# Sheet2.net
KiCad netlist of a schematic drawn in Altium Designer
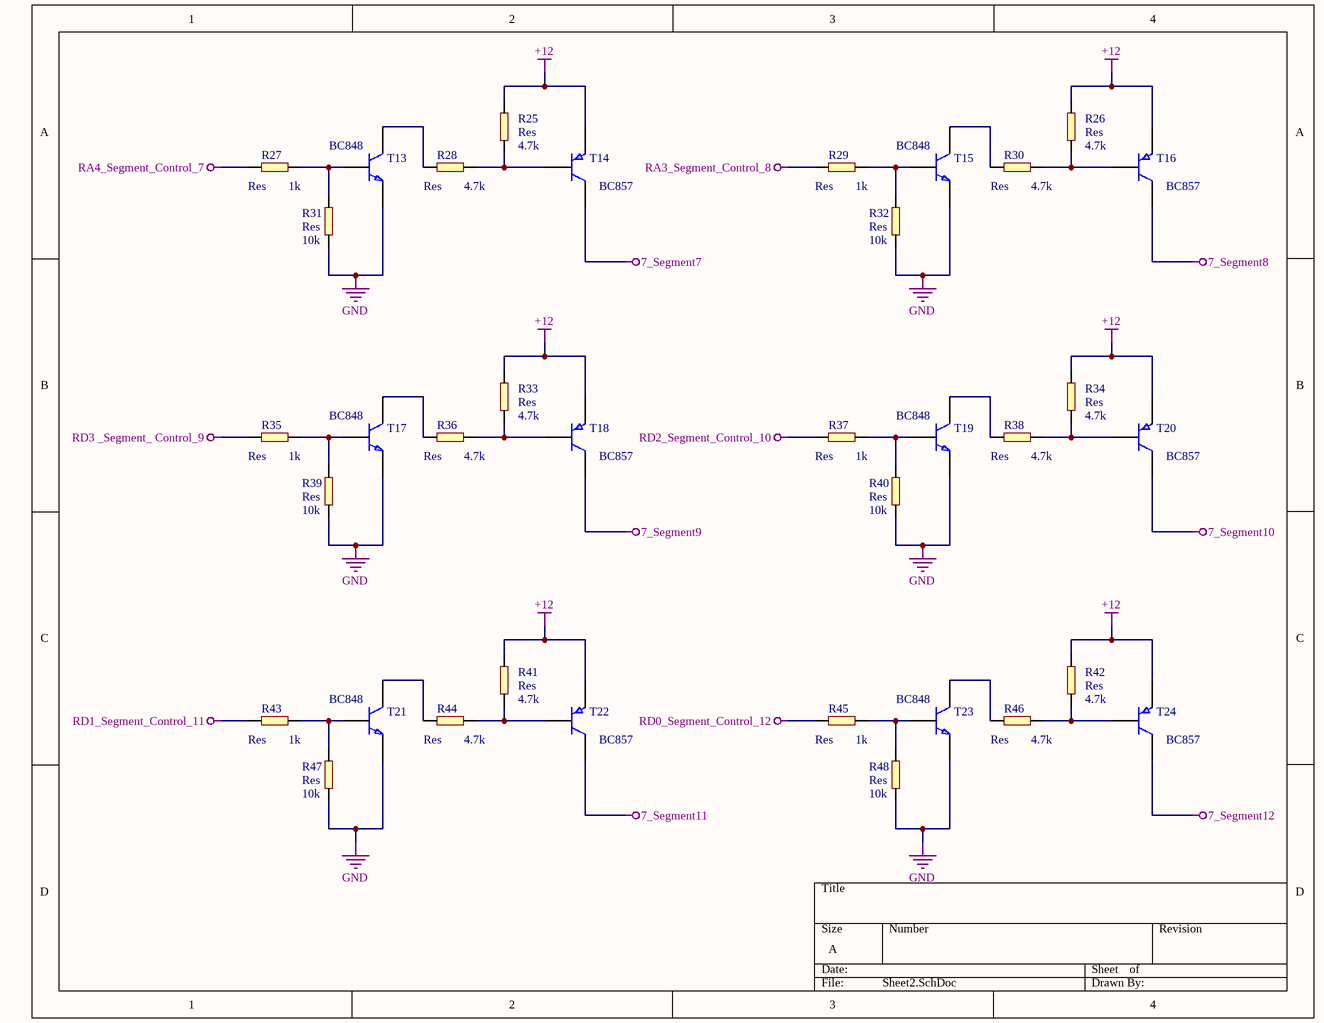
[diagram p0: Sheet2.SchDoc]

(export (version "E")
  (design (tool "Eeschema 10.0.6"))
  (components
    (comp (ref "R25")
      (value "Res")
      (footprint "RES0805")
      (description "Res0805")
      (fields (field (name "ALTIUM_VALUE") "4.7k"))
      (libsource (lib "") (part "Resistor_1"))
    )
    (comp (ref "R26")
      (value "Res")
      (footprint "RES0805")
      (description "Res0805")
      (fields (field (name "ALTIUM_VALUE") "4.7k"))
      (libsource (lib "") (part "Resistor_1"))
    )
    (comp (ref "R27")
      (value "Res")
      (footprint "RES0805")
      (description "Res0805")
      (fields (field (name "ALTIUM_VALUE") "1k"))
      (libsource (lib "Dinesh_New_Integrated_Library") (part "Resistor"))
    )
    (comp (ref "R28")
      (value "Res")
      (footprint "RES0805")
      (description "Res0805")
      (fields (field (name "ALTIUM_VALUE") "4.7k"))
      (libsource (lib "Dinesh_New_Integrated_Library") (part "Resistor"))
    )
    (comp (ref "R29")
      (value "Res")
      (footprint "RES0805")
      (description "Res0805")
      (fields (field (name "ALTIUM_VALUE") "1k"))
      (libsource (lib "Dinesh_New_Integrated_Library") (part "Resistor"))
    )
    (comp (ref "R30")
      (value "Res")
      (footprint "RES0805")
      (description "Res0805")
      (fields (field (name "ALTIUM_VALUE") "4.7k"))
      (libsource (lib "Dinesh_New_Integrated_Library") (part "Resistor"))
    )
    (comp (ref "R31")
      (value "Res")
      (footprint "RES0805")
      (description "Res0805")
      (fields (field (name "ALTIUM_VALUE") "10k"))
      (libsource (lib "") (part "Resistor_2"))
    )
    (comp (ref "R32")
      (value "Res")
      (footprint "RES0805")
      (description "Res0805")
      (fields (field (name "ALTIUM_VALUE") "10k"))
      (libsource (lib "") (part "Resistor_2"))
    )
    (comp (ref "R33")
      (value "Res")
      (footprint "RES0805")
      (description "Res0805")
      (fields (field (name "ALTIUM_VALUE") "4.7k"))
      (libsource (lib "") (part "Resistor_1"))
    )
    (comp (ref "R34")
      (value "Res")
      (footprint "RES0805")
      (description "Res0805")
      (fields (field (name "ALTIUM_VALUE") "4.7k"))
      (libsource (lib "") (part "Resistor_1"))
    )
    (comp (ref "R35")
      (value "Res")
      (footprint "RES0805")
      (description "Res0805")
      (fields (field (name "ALTIUM_VALUE") "1k"))
      (libsource (lib "Dinesh_New_Integrated_Library") (part "Resistor"))
    )
    (comp (ref "R36")
      (value "Res")
      (footprint "RES0805")
      (description "Res0805")
      (fields (field (name "ALTIUM_VALUE") "4.7k"))
      (libsource (lib "Dinesh_New_Integrated_Library") (part "Resistor"))
    )
    (comp (ref "R37")
      (value "Res")
      (footprint "RES0805")
      (description "Res0805")
      (fields (field (name "ALTIUM_VALUE") "1k"))
      (libsource (lib "Dinesh_New_Integrated_Library") (part "Resistor"))
    )
    (comp (ref "R38")
      (value "Res")
      (footprint "RES0805")
      (description "Res0805")
      (fields (field (name "ALTIUM_VALUE") "4.7k"))
      (libsource (lib "Dinesh_New_Integrated_Library") (part "Resistor"))
    )
    (comp (ref "R39")
      (value "Res")
      (footprint "RES0805")
      (description "Res0805")
      (fields (field (name "ALTIUM_VALUE") "10k"))
      (libsource (lib "") (part "Resistor_2"))
    )
    (comp (ref "R40")
      (value "Res")
      (footprint "RES0805")
      (description "Res0805")
      (fields (field (name "ALTIUM_VALUE") "10k"))
      (libsource (lib "") (part "Resistor_2"))
    )
    (comp (ref "R41")
      (value "Res")
      (footprint "RES0805")
      (description "Res0805")
      (fields (field (name "ALTIUM_VALUE") "4.7k"))
      (libsource (lib "") (part "Resistor_1"))
    )
    (comp (ref "R42")
      (value "Res")
      (footprint "RES0805")
      (description "Res0805")
      (fields (field (name "ALTIUM_VALUE") "4.7k"))
      (libsource (lib "") (part "Resistor_1"))
    )
    (comp (ref "R43")
      (value "Res")
      (footprint "RES0805")
      (description "Res0805")
      (fields (field (name "ALTIUM_VALUE") "1k"))
      (libsource (lib "Dinesh_New_Integrated_Library") (part "Resistor"))
    )
    (comp (ref "R44")
      (value "Res")
      (footprint "RES0805")
      (description "Res0805")
      (fields (field (name "ALTIUM_VALUE") "4.7k"))
      (libsource (lib "Dinesh_New_Integrated_Library") (part "Resistor"))
    )
    (comp (ref "R45")
      (value "Res")
      (footprint "RES0805")
      (description "Res0805")
      (fields (field (name "ALTIUM_VALUE") "1k"))
      (libsource (lib "Dinesh_New_Integrated_Library") (part "Resistor"))
    )
    (comp (ref "R46")
      (value "Res")
      (footprint "RES0805")
      (description "Res0805")
      (fields (field (name "ALTIUM_VALUE") "4.7k"))
      (libsource (lib "Dinesh_New_Integrated_Library") (part "Resistor"))
    )
    (comp (ref "R47")
      (value "Res")
      (footprint "RES0805")
      (description "Res0805")
      (fields (field (name "ALTIUM_VALUE") "10k"))
      (libsource (lib "") (part "Resistor_2"))
    )
    (comp (ref "R48")
      (value "Res")
      (footprint "RES0805")
      (description "Res0805")
      (fields (field (name "ALTIUM_VALUE") "10k"))
      (libsource (lib "") (part "Resistor_2"))
    )
    (comp (ref "T13")
      (value "BC848")
      (footprint "SOT23")
      (description "TRANSISTOR")
      (libsource (lib "Dinesh_New_Integrated_Library") (part "BC848"))
    )
    (comp (ref "T14")
      (value "BC857")
      (footprint "SOT23")
      (libsource (lib "Dinesh_New_Integrated_Library") (part "BC857"))
    )
    (comp (ref "T15")
      (value "BC848")
      (footprint "SOT23")
      (description "TRANSISTOR")
      (libsource (lib "Dinesh_New_Integrated_Library") (part "BC848"))
    )
    (comp (ref "T16")
      (value "BC857")
      (footprint "SOT23")
      (libsource (lib "Dinesh_New_Integrated_Library") (part "BC857"))
    )
    (comp (ref "T17")
      (value "BC848")
      (footprint "SOT23")
      (description "TRANSISTOR")
      (libsource (lib "Dinesh_New_Integrated_Library") (part "BC848"))
    )
    (comp (ref "T18")
      (value "BC857")
      (footprint "SOT23")
      (libsource (lib "Dinesh_New_Integrated_Library") (part "BC857"))
    )
    (comp (ref "T19")
      (value "BC848")
      (footprint "SOT23")
      (description "TRANSISTOR")
      (libsource (lib "Dinesh_New_Integrated_Library") (part "BC848"))
    )
    (comp (ref "T20")
      (value "BC857")
      (footprint "SOT23")
      (libsource (lib "Dinesh_New_Integrated_Library") (part "BC857"))
    )
    (comp (ref "T21")
      (value "BC848")
      (footprint "SOT23")
      (description "TRANSISTOR")
      (libsource (lib "Dinesh_New_Integrated_Library") (part "BC848"))
    )
    (comp (ref "T22")
      (value "BC857")
      (footprint "SOT23")
      (libsource (lib "Dinesh_New_Integrated_Library") (part "BC857"))
    )
    (comp (ref "T23")
      (value "BC848")
      (footprint "SOT23")
      (description "TRANSISTOR")
      (libsource (lib "Dinesh_New_Integrated_Library") (part "BC848"))
    )
    (comp (ref "T24")
      (value "BC857")
      (footprint "SOT23")
      (libsource (lib "Dinesh_New_Integrated_Library") (part "BC857"))
    )
  )
  (nets
    (net (code "1") (name "+12") (class "Default")
      (node (ref "R25") (pin "2") (pinfunction "b_2") (pintype "passive"))
      (node (ref "R26") (pin "2") (pinfunction "b_2") (pintype "passive"))
      (node (ref "R33") (pin "2") (pinfunction "b_2") (pintype "passive"))
      (node (ref "R34") (pin "2") (pinfunction "b_2") (pintype "passive"))
      (node (ref "R41") (pin "2") (pinfunction "b_2") (pintype "passive"))
      (node (ref "R42") (pin "2") (pinfunction "b_2") (pintype "passive"))
      (node (ref "T14") (pin "2") (pinfunction "E_2") (pintype "passive"))
      (node (ref "T16") (pin "2") (pinfunction "E_2") (pintype "passive"))
      (node (ref "T18") (pin "2") (pinfunction "E_2") (pintype "passive"))
      (node (ref "T20") (pin "2") (pinfunction "E_2") (pintype "passive"))
      (node (ref "T22") (pin "2") (pinfunction "E_2") (pintype "passive"))
      (node (ref "T24") (pin "2") (pinfunction "E_2") (pintype "passive"))
    )
    (net (code "2") (name "7_Segment7") (class "Default")
      (node (ref "T14") (pin "3") (pinfunction "C_3") (pintype "passive"))
    )
    (net (code "3") (name "7_Segment8") (class "Default")
      (node (ref "T16") (pin "3") (pinfunction "C_3") (pintype "passive"))
    )
    (net (code "4") (name "7_Segment9") (class "Default")
      (node (ref "T18") (pin "3") (pinfunction "C_3") (pintype "passive"))
    )
    (net (code "5") (name "7_Segment10") (class "Default")
      (node (ref "T20") (pin "3") (pinfunction "C_3") (pintype "passive"))
    )
    (net (code "6") (name "7_Segment11") (class "Default")
      (node (ref "T22") (pin "3") (pinfunction "C_3") (pintype "passive"))
    )
    (net (code "7") (name "7_Segment12") (class "Default")
      (node (ref "T24") (pin "3") (pinfunction "C_3") (pintype "passive"))
    )
    (net (code "8") (name "GND") (class "Default")
      (node (ref "R31") (pin "2") (pinfunction "b_2") (pintype "passive"))
      (node (ref "R32") (pin "2") (pinfunction "b_2") (pintype "passive"))
      (node (ref "R39") (pin "2") (pinfunction "b_2") (pintype "passive"))
      (node (ref "R40") (pin "2") (pinfunction "b_2") (pintype "passive"))
      (node (ref "R47") (pin "2") (pinfunction "b_2") (pintype "passive"))
      (node (ref "R48") (pin "2") (pinfunction "b_2") (pintype "passive"))
      (node (ref "T13") (pin "2") (pinfunction "E_2") (pintype "passive"))
      (node (ref "T15") (pin "2") (pinfunction "E_2") (pintype "passive"))
      (node (ref "T17") (pin "2") (pinfunction "E_2") (pintype "passive"))
      (node (ref "T19") (pin "2") (pinfunction "E_2") (pintype "passive"))
      (node (ref "T21") (pin "2") (pinfunction "E_2") (pintype "passive"))
      (node (ref "T23") (pin "2") (pinfunction "E_2") (pintype "passive"))
    )
    (net (code "9") (name "Net-(R25-a)") (class "Default")
      (node (ref "R25") (pin "1") (pinfunction "a_1") (pintype "passive"))
      (node (ref "R28") (pin "1") (pinfunction "a_1") (pintype "passive"))
      (node (ref "T14") (pin "1") (pinfunction "B_1") (pintype "passive"))
    )
    (net (code "10") (name "Net-(R26-a)") (class "Default")
      (node (ref "R26") (pin "1") (pinfunction "a_1") (pintype "passive"))
      (node (ref "R30") (pin "1") (pinfunction "a_1") (pintype "passive"))
      (node (ref "T16") (pin "1") (pinfunction "B_1") (pintype "passive"))
    )
    (net (code "11") (name "Net-(R27-a)") (class "Default")
      (node (ref "R27") (pin "1") (pinfunction "a_1") (pintype "passive"))
      (node (ref "R31") (pin "1") (pinfunction "a_1") (pintype "passive"))
      (node (ref "T13") (pin "1") (pinfunction "B_1") (pintype "passive"))
    )
    (net (code "12") (name "Net-(R28-b)") (class "Default")
      (node (ref "R28") (pin "2") (pinfunction "b_2") (pintype "passive"))
      (node (ref "T13") (pin "3") (pinfunction "C_3") (pintype "passive"))
    )
    (net (code "13") (name "Net-(R29-a)") (class "Default")
      (node (ref "R29") (pin "1") (pinfunction "a_1") (pintype "passive"))
      (node (ref "R32") (pin "1") (pinfunction "a_1") (pintype "passive"))
      (node (ref "T15") (pin "1") (pinfunction "B_1") (pintype "passive"))
    )
    (net (code "14") (name "Net-(R30-b)") (class "Default")
      (node (ref "R30") (pin "2") (pinfunction "b_2") (pintype "passive"))
      (node (ref "T15") (pin "3") (pinfunction "C_3") (pintype "passive"))
    )
    (net (code "15") (name "Net-(R33-a)") (class "Default")
      (node (ref "R33") (pin "1") (pinfunction "a_1") (pintype "passive"))
      (node (ref "R36") (pin "1") (pinfunction "a_1") (pintype "passive"))
      (node (ref "T18") (pin "1") (pinfunction "B_1") (pintype "passive"))
    )
    (net (code "16") (name "Net-(R34-a)") (class "Default")
      (node (ref "R34") (pin "1") (pinfunction "a_1") (pintype "passive"))
      (node (ref "R38") (pin "1") (pinfunction "a_1") (pintype "passive"))
      (node (ref "T20") (pin "1") (pinfunction "B_1") (pintype "passive"))
    )
    (net (code "17") (name "Net-(R35-a)") (class "Default")
      (node (ref "R35") (pin "1") (pinfunction "a_1") (pintype "passive"))
      (node (ref "R39") (pin "1") (pinfunction "a_1") (pintype "passive"))
      (node (ref "T17") (pin "1") (pinfunction "B_1") (pintype "passive"))
    )
    (net (code "18") (name "Net-(R36-b)") (class "Default")
      (node (ref "R36") (pin "2") (pinfunction "b_2") (pintype "passive"))
      (node (ref "T17") (pin "3") (pinfunction "C_3") (pintype "passive"))
    )
    (net (code "19") (name "Net-(R37-a)") (class "Default")
      (node (ref "R37") (pin "1") (pinfunction "a_1") (pintype "passive"))
      (node (ref "R40") (pin "1") (pinfunction "a_1") (pintype "passive"))
      (node (ref "T19") (pin "1") (pinfunction "B_1") (pintype "passive"))
    )
    (net (code "20") (name "Net-(R38-b)") (class "Default")
      (node (ref "R38") (pin "2") (pinfunction "b_2") (pintype "passive"))
      (node (ref "T19") (pin "3") (pinfunction "C_3") (pintype "passive"))
    )
    (net (code "21") (name "Net-(R41-a)") (class "Default")
      (node (ref "R41") (pin "1") (pinfunction "a_1") (pintype "passive"))
      (node (ref "R44") (pin "1") (pinfunction "a_1") (pintype "passive"))
      (node (ref "T22") (pin "1") (pinfunction "B_1") (pintype "passive"))
    )
    (net (code "22") (name "Net-(R42-a)") (class "Default")
      (node (ref "R42") (pin "1") (pinfunction "a_1") (pintype "passive"))
      (node (ref "R46") (pin "1") (pinfunction "a_1") (pintype "passive"))
      (node (ref "T24") (pin "1") (pinfunction "B_1") (pintype "passive"))
    )
    (net (code "23") (name "Net-(R43-a)") (class "Default")
      (node (ref "R43") (pin "1") (pinfunction "a_1") (pintype "passive"))
      (node (ref "R47") (pin "1") (pinfunction "a_1") (pintype "passive"))
      (node (ref "T21") (pin "1") (pinfunction "B_1") (pintype "passive"))
    )
    (net (code "24") (name "Net-(R44-b)") (class "Default")
      (node (ref "R44") (pin "2") (pinfunction "b_2") (pintype "passive"))
      (node (ref "T21") (pin "3") (pinfunction "C_3") (pintype "passive"))
    )
    (net (code "25") (name "Net-(R45-a)") (class "Default")
      (node (ref "R45") (pin "1") (pinfunction "a_1") (pintype "passive"))
      (node (ref "R48") (pin "1") (pinfunction "a_1") (pintype "passive"))
      (node (ref "T23") (pin "1") (pinfunction "B_1") (pintype "passive"))
    )
    (net (code "26") (name "Net-(R46-b)") (class "Default")
      (node (ref "R46") (pin "2") (pinfunction "b_2") (pintype "passive"))
      (node (ref "T23") (pin "3") (pinfunction "C_3") (pintype "passive"))
    )
    (net (code "27") (name "RA3_Segment_Control_8") (class "Default")
      (node (ref "R29") (pin "2") (pinfunction "b_2") (pintype "passive"))
    )
    (net (code "28") (name "RA4_Segment_Control_7") (class "Default")
      (node (ref "R27") (pin "2") (pinfunction "b_2") (pintype "passive"))
    )
    (net (code "29") (name "RD0_Segment_Control_12") (class "Default")
      (node (ref "R45") (pin "2") (pinfunction "b_2") (pintype "passive"))
    )
    (net (code "30") (name "RD1_Segment_Control_11") (class "Default")
      (node (ref "R43") (pin "2") (pinfunction "b_2") (pintype "passive"))
    )
    (net (code "31") (name "RD2_Segment_Control_10") (class "Default")
      (node (ref "R37") (pin "2") (pinfunction "b_2") (pintype "passive"))
    )
    (net (code "32") (name "RD3 _Segment_ Control_9") (class "Default")
      (node (ref "R35") (pin "2") (pinfunction "b_2") (pintype "passive"))
    )
  )
)
